# MCORD_AFE_EXT.net
KiCad netlist of a schematic drawn in Altium Designer
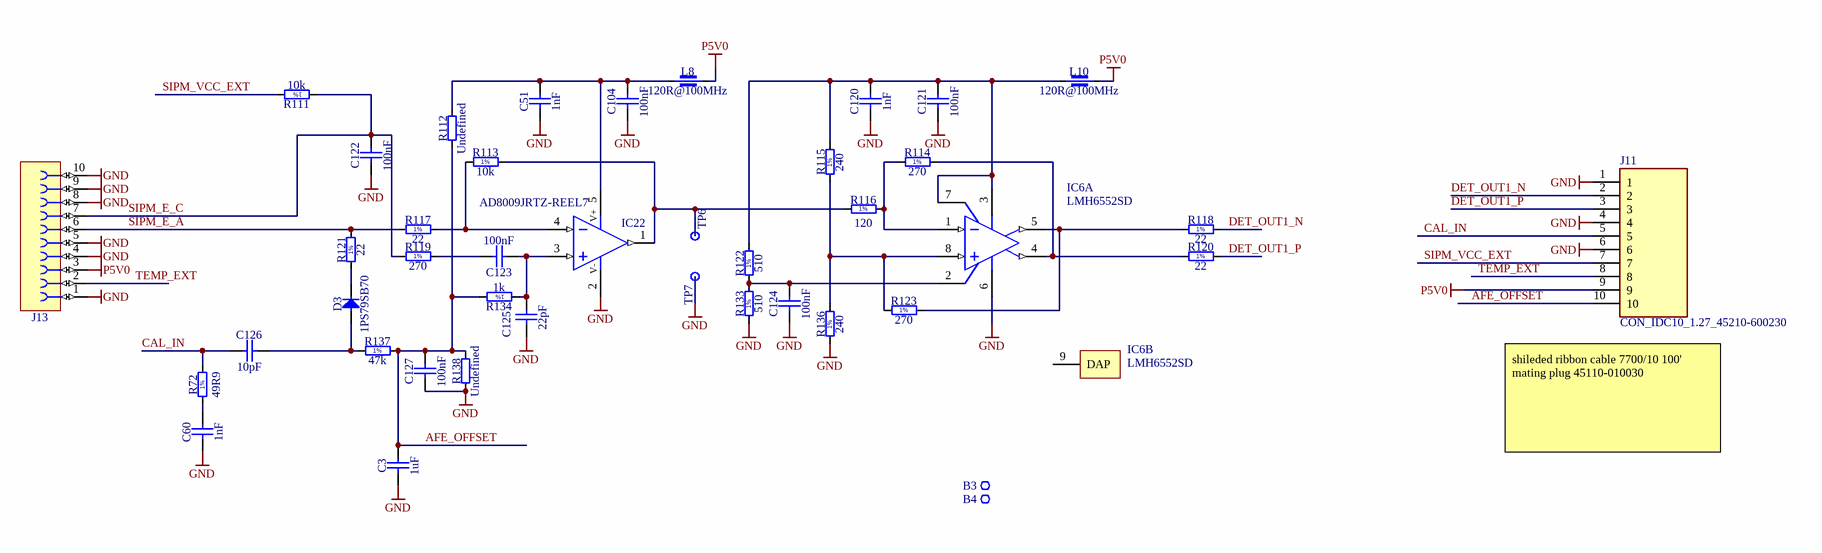
[diagram p0: MCORD_AFE_EXT.SchDoc]

(export (version "E")
  (design (tool "Eeschema 10.0.6"))
  (components
    (comp (ref "B3")
      (value "Plated Hole")
      (footprint "MTG320_550")
      (description "Single Terminal Socket")
      (fields (field (name "PART NUMBER") "PLATED_HOLE3.2_PAD5.5") (field (name "AUTHOR") "CERN DEM JMW"))
      (libsource (lib "Eletro-mechanical") (part "Single Terminal Socket"))
    )
    (comp (ref "B4")
      (value "Plated Hole")
      (footprint "MTG320_550")
      (description "Single Terminal Socket")
      (fields (field (name "PART NUMBER") "PLATED_HOLE3.2_PAD5.5") (field (name "AUTHOR") "CERN DEM JMW"))
      (libsource (lib "Eletro-mechanical") (part "Single Terminal Socket"))
    )
    (comp (ref "C3")
      (value "1uF")
      (footprint "CAPC1608X87N")
      (description "Non-polarised capacitor")
      (fields
        (field (name "PART NUMBER") "CC0603_1UF_16V_10%_X7R")
        (field (name "VOLTAGE") "16V")
        (field (name "AUTHOR") "CERN DEM JLC")
      )
      (libsource (lib "Capacitors") (part "Capacitor - non polarized"))
    )
    (comp (ref "C51")
      (value "1nF")
      (footprint "CAPC1005X55N")
      (description "Non-polarised capacitor")
      (fields
        (field (name "PART NUMBER") "CC0402_1NF_50V_5%_C0G")
        (field (name "VOLTAGE") "50V")
        (field (name "AUTHOR") "CERN DEM BC")
      )
      (libsource (lib "Capacitors") (part "Capacitor - non polarized"))
    )
    (comp (ref "C60")
      (value "1nF")
      (footprint "CAPC1005X55N")
      (description "Non-polarised capacitor")
      (fields
        (field (name "PART NUMBER") "CC0402_1NF_50V_5%_C0G")
        (field (name "VOLTAGE") "50V")
        (field (name "AUTHOR") "CERN DEM BC")
      )
      (libsource (lib "Capacitors") (part "Capacitor - non polarized"))
    )
    (comp (ref "C104")
      (value "100nF")
      (footprint "CAPC1005X55N")
      (description "Non-polarised capacitor")
      (fields
        (field (name "PART NUMBER") "CC0402_100NF_16V_10%_X7R")
        (field (name "VOLTAGE") "16V")
        (field (name "AUTHOR") "CERN DEM JLC")
      )
      (libsource (lib "Capacitors") (part "Capacitor - non polarized"))
    )
    (comp (ref "C120")
      (value "1nF")
      (footprint "CAPC1005X55N")
      (description "Non-polarised capacitor")
      (fields
        (field (name "PART NUMBER") "CC0402_1NF_50V_5%_C0G")
        (field (name "VOLTAGE") "50V")
        (field (name "AUTHOR") "CERN DEM BC")
      )
      (libsource (lib "Capacitors") (part "Capacitor - non polarized"))
    )
    (comp (ref "C121")
      (value "100nF")
      (footprint "CAPC1005X55N")
      (description "Non-polarised capacitor")
      (fields
        (field (name "PART NUMBER") "CC0402_100NF_16V_10%_X7R")
        (field (name "VOLTAGE") "16V")
        (field (name "AUTHOR") "CERN DEM JLC")
      )
      (libsource (lib "Capacitors") (part "Capacitor - non polarized"))
    )
    (comp (ref "C122")
      (value "100nF")
      (footprint "CAPC1608X90N")
      (description "Non-polarised capacitor")
      (fields
        (field (name "PART NUMBER") "CC0603_100NF_100V_10%_X7R")
        (field (name "VOLTAGE") "100V")
        (field (name "AUTHOR") "CERN DEM JLC")
      )
      (libsource (lib "Capacitors") (part "Capacitor - non polarized"))
    )
    (comp (ref "C123")
      (value "100nF")
      (footprint "CAPC1608X90N")
      (description "Non-polarised capacitor")
      (fields
        (field (name "PART NUMBER") "CC0603_100NF_100V_10%_X7R")
        (field (name "VOLTAGE") "100V")
        (field (name "AUTHOR") "CERN DEM JLC")
      )
      (libsource (lib "Capacitors") (part "Capacitor - non polarized"))
    )
    (comp (ref "C124")
      (value "100nF")
      (footprint "CAPC1005X55N")
      (description "Non-polarised capacitor")
      (fields
        (field (name "PART NUMBER") "CC0402_100NF_16V_10%_X7R")
        (field (name "VOLTAGE") "16V")
        (field (name "AUTHOR") "CERN DEM JLC")
      )
      (libsource (lib "Capacitors") (part "Capacitor - non polarized"))
    )
    (comp (ref "C125")
      (value "22pF")
      (footprint "CAPC1005X55N")
      (description "Non-polarised capacitor")
      (fields
        (field (name "PART NUMBER") "CC0402_22PF_50V_5%_C0G")
        (field (name "VOLTAGE") "50V")
        (field (name "AUTHOR") "CERN DEM JLC")
      )
      (libsource (lib "Capacitors") (part "Capacitor - non polarized"))
    )
    (comp (ref "C126")
      (value "10pF")
      (footprint "CAPC1608X87N")
      (description "Non-polarised capacitor")
      (fields
        (field (name "PART NUMBER") "CC0603_10PF_50V_5%_NP0")
        (field (name "VOLTAGE") "50V")
        (field (name "AUTHOR") "CERN DEM JLC")
      )
      (libsource (lib "Capacitors") (part "Capacitor - non polarized"))
    )
    (comp (ref "C127")
      (value "100nF")
      (footprint "CAPC1005X55N")
      (description "Non-polarised capacitor")
      (fields
        (field (name "PART NUMBER") "CC0402_100NF_16V_10%_X7R")
        (field (name "VOLTAGE") "16V")
        (field (name "AUTHOR") "CERN DEM JLC")
      )
      (libsource (lib "Capacitors") (part "Capacitor - non polarized"))
    )
    (comp (ref "D3")
      (value "1PS79SB70")
      (footprint "SODFL1608X65N")
      (description "Diode")
      (fields (field (name "VOLTAGE") "70V") (field (name "POWER") "70mA") (field (name "AUTHOR") "GK"))
      (libsource (lib "Diodes") (part "D_1PS79SB70"))
    )
    (comp (ref "IC6")
      (value "LMH6552SD")
      (footprint "SDA08C")
      (description "1.5 GHz Fully Differential Amplifier, 8-pin LLP")
      (fields (field (name "MANUFACTURER") "National Semiconductor"))
      (libsource (lib "Altium Content Vault") (part "AMP-DIFA-LMH6552-9"))
    )
    (comp (ref "IC22")
      (value "AD8009JRTZ-REEL7")
      (footprint "SOT95P280X145-5N")
      (description "Operational Amplifier")
      (fields (field (name "MANUFACTURER") "ANALOG DEVICES") (field (name "AUTHOR") "CERN DEM JLC"))
      (libsource (lib "ICs And Semiconductors") (part "Operational Amplifier Type7"))
    )
    (comp (ref "J11")
      (value "CON_IDC10_1.27_45210-600230")
      (footprint "SamacSys:SHDR10W38P127_2X5_1069X594X747P")
      (description "Connector")
      (fields
        (field (name "MANUFACTURER_PART_NUMBER") "45210-600230")
        (field (name "MOUSER PART NUMBER") "517-45210-600230")
      )
      (libsource (lib "LIBRARY_SCH") (part "CON_IDC10_1.27_45210-600230"))
    )
    (comp (ref "J13")
      (value "FFC/FPC")
      (footprint "MOLEX_52745-1097")
      (description "Connector 10 Female")
      (fields
        (field (name "PART NUMBER") "MOLEX_52745-1097")
        (field (name "MANUFACTURER") "MOLEX")
        (field (name "AUTHOR") "CERN DEM JLC")
      )
      (libsource (lib "Connectors") (part "Connector 10 Female"))
    )
    (comp (ref "L8")
      (value "120R@100MHz")
      (footprint "INDC1005X55N")
      (fields
        (field (name "PART NUMBER") "IND0402_MURATA_BLM15PX121SN1D")
        (field (name "POWER") "2A")
        (field (name "TOLERANCE") "±25%")
        (field (name "AUTHOR") "CERN DEM JMW")
      )
      (libsource (lib "Inductors & Transformers") (part "Ferrite Bead"))
    )
    (comp (ref "L10")
      (value "120R@100MHz")
      (footprint "INDC1005X55N")
      (fields
        (field (name "PART NUMBER") "IND0402_MURATA_BLM15PX121SN1D")
        (field (name "POWER") "2A")
        (field (name "TOLERANCE") "±25%")
        (field (name "AUTHOR") "CERN DEM JMW")
      )
      (libsource (lib "Inductors & Transformers") (part "Ferrite Bead"))
    )
    (comp (ref "R72")
      (value "49R9")
      (footprint "RESC1005X40N")
      (description "Resistor - 1%")
      (fields
        (field (name "PART NUMBER") "R0402_49R9_1%_0.0625W_100PPM")
        (field (name "POWER") "0.0625W")
        (field (name "AUTHOR") "CERN DEM JLC")
      )
      (libsource (lib "Resistors") (part "Resistor - 1%"))
    )
    (comp (ref "R111")
      (value "10k")
      (footprint "RESC1005X40N")
      (description "Resistor - 1%")
      (fields
        (field (name "PART NUMBER") "R0402_10K_1%_0.0625W_100PPM")
        (field (name "POWER") "0.0625W")
        (field (name "AUTHOR") "CERN DEM JLC")
      )
      (libsource (lib "Resistors") (part "Resistor - 1%"))
    )
    (comp (ref "R112")
      (value "Undefined")
      (footprint "RESC1005X40N")
      (description "Resistor")
      (fields (field (name "PART NUMBER") "R0402_NO-VALUE") (field (name "AUTHOR") "CERN DEM JLC"))
      (libsource (lib "Resistors") (part "Resistor"))
    )
    (comp (ref "R113")
      (value "10k")
      (footprint "RESC1005X40N")
      (description "Resistor - 1%")
      (fields
        (field (name "PART NUMBER") "R0402_10K_1%_0.0625W_100PPM")
        (field (name "POWER") "0.0625W")
        (field (name "AUTHOR") "CERN DEM JLC")
      )
      (libsource (lib "Resistors") (part "Resistor - 1%"))
    )
    (comp (ref "R114")
      (value "270")
      (footprint "RESC1005X40N")
      (description "Resistor - 1%")
      (fields
        (field (name "PART NUMBER") "R0402_270R_1%_0.0625W_100PPM")
        (field (name "POWER") "0.0625W")
        (field (name "AUTHOR") "CERN DEM JLC")
      )
      (libsource (lib "Resistors") (part "Resistor - 1%"))
    )
    (comp (ref "R115")
      (value "240")
      (footprint "RESC1005X40N")
      (description "Resistor - 1%")
      (fields
        (field (name "PART NUMBER") "R0402_240R_1%_0.0625W_100PPM")
        (field (name "POWER") "0.0625W")
        (field (name "AUTHOR") "CERN DEM JLC")
      )
      (libsource (lib "Resistors") (part "Resistor - 1%"))
    )
    (comp (ref "R116")
      (value "120")
      (footprint "RESC1005X40N")
      (description "Resistor - 1%")
      (fields
        (field (name "PART NUMBER") "R0402_120R_1%_0.0625W_100PPM")
        (field (name "POWER") "0.0625W")
        (field (name "AUTHOR") "CERN DEM JLC")
      )
      (libsource (lib "Resistors") (part "Resistor - 1%"))
    )
    (comp (ref "R117")
      (value "22")
      (footprint "RESC1608X55N")
      (description "Resistor - 1%")
      (fields
        (field (name "PART NUMBER") "R0603_22R_1%_0.1W_100PPM")
        (field (name "POWER") "0.1W")
        (field (name "AUTHOR") "CERN DEM JLC")
      )
      (libsource (lib "Resistors") (part "Resistor - 1%"))
    )
    (comp (ref "R118")
      (value "22")
      (footprint "RESC1608X55N")
      (description "Resistor - 1%")
      (fields
        (field (name "PART NUMBER") "R0603_22R_1%_0.1W_100PPM")
        (field (name "POWER") "0.1W")
        (field (name "AUTHOR") "CERN DEM JLC")
      )
      (libsource (lib "Resistors") (part "Resistor - 1%"))
    )
    (comp (ref "R119")
      (value "270")
      (footprint "RESC1005X40N")
      (description "Resistor - 1%")
      (fields
        (field (name "PART NUMBER") "R0402_270R_1%_0.0625W_100PPM")
        (field (name "POWER") "0.0625W")
        (field (name "AUTHOR") "CERN DEM JLC")
      )
      (libsource (lib "Resistors") (part "Resistor - 1%"))
    )
    (comp (ref "R120")
      (value "22")
      (footprint "RESC1608X55N")
      (description "Resistor - 1%")
      (fields
        (field (name "PART NUMBER") "R0603_22R_1%_0.1W_100PPM")
        (field (name "POWER") "0.1W")
        (field (name "AUTHOR") "CERN DEM JLC")
      )
      (libsource (lib "Resistors") (part "Resistor - 1%"))
    )
    (comp (ref "R121")
      (value "22")
      (footprint "RESC1608X55N")
      (description "Resistor - 1%")
      (fields
        (field (name "PART NUMBER") "R0603_22R_1%_0.1W_100PPM")
        (field (name "POWER") "0.1W")
        (field (name "AUTHOR") "CERN DEM JLC")
      )
      (libsource (lib "Resistors") (part "Resistor - 1%"))
    )
    (comp (ref "R122")
      (value "510")
      (footprint "RESC1005X40N")
      (description "Resistor - 1%")
      (fields
        (field (name "PART NUMBER") "R0402_510R_1%_0.0625W_100PPM")
        (field (name "POWER") "0.0625W")
        (field (name "AUTHOR") "CERN DEM JLC")
      )
      (libsource (lib "Resistors") (part "Resistor - 1%"))
    )
    (comp (ref "R123")
      (value "270")
      (footprint "RESC1005X40N")
      (description "Resistor - 1%")
      (fields
        (field (name "PART NUMBER") "R0402_270R_1%_0.0625W_100PPM")
        (field (name "POWER") "0.0625W")
        (field (name "AUTHOR") "CERN DEM JLC")
      )
      (libsource (lib "Resistors") (part "Resistor - 1%"))
    )
    (comp (ref "R133")
      (value "510")
      (footprint "RESC1005X40N")
      (description "Resistor - 1%")
      (fields
        (field (name "PART NUMBER") "R0402_510R_1%_0.0625W_100PPM")
        (field (name "POWER") "0.0625W")
        (field (name "AUTHOR") "CERN DEM JLC")
      )
      (libsource (lib "Resistors") (part "Resistor - 1%"))
    )
    (comp (ref "R134")
      (value "1k")
      (footprint "RESC1005X40N")
      (description "Resistor - 1%")
      (fields
        (field (name "PART NUMBER") "R0402_1K_1%_0.0625W_100PPM")
        (field (name "POWER") "0.0625W")
        (field (name "AUTHOR") "CERN DEM JLC")
      )
      (libsource (lib "Resistors") (part "Resistor - 1%"))
    )
    (comp (ref "R136")
      (value "240")
      (footprint "RESC1005X40N")
      (description "Resistor - 1%")
      (fields
        (field (name "PART NUMBER") "R0402_240R_1%_0.0625W_100PPM")
        (field (name "POWER") "0.0625W")
        (field (name "AUTHOR") "CERN DEM JLC")
      )
      (libsource (lib "Resistors") (part "Resistor - 1%"))
    )
    (comp (ref "R137")
      (value "47k")
      (footprint "RESC1005X40N")
      (description "Resistor - 1%")
      (fields
        (field (name "PART NUMBER") "R0402_47K_1%_0.0625W_100PPM")
        (field (name "POWER") "0.0625W")
        (field (name "AUTHOR") "CERN DEM JLC")
      )
      (libsource (lib "Resistors") (part "Resistor - 1%"))
    )
    (comp (ref "R138")
      (value "Undefined")
      (footprint "RESC1005X40N")
      (description "Resistor")
      (fields (field (name "PART NUMBER") "R0402_NO-VALUE") (field (name "AUTHOR") "CERN DEM JLC"))
      (libsource (lib "Resistors") (part "Resistor"))
    )
    (comp (ref "TP6")
      (value "Test Point")
      (footprint "TPS127")
      (fields (field (name "PART NUMBER") "SMD_PAD_1.27X1.27MM") (field (name "AUTHOR") "CERN DEM JLC"))
      (libsource (lib "Eletro-mechanical") (part "Test Point"))
    )
    (comp (ref "TP7")
      (value "Test Point")
      (footprint "TPS127")
      (fields (field (name "PART NUMBER") "SMD_PAD_1.27X1.27MM") (field (name "AUTHOR") "CERN DEM JLC"))
      (libsource (lib "Eletro-mechanical") (part "Test Point"))
    )
  )
  (nets
    (net (code "1") (name "/AFE_OFFSET") (class "Default")
      (node (ref "C127") (pin "2") (pinfunction "2_2") (pintype "passive"))
      (node (ref "C3") (pin "2") (pinfunction "2_2") (pintype "passive"))
      (node (ref "J11") (pin "10") (pinfunction "10_10") (pintype "passive"))
      (node (ref "R112") (pin "1") (pinfunction "1_1") (pintype "passive"))
      (node (ref "R134") (pin "2") (pinfunction "2_2") (pintype "passive"))
      (node (ref "R137") (pin "2") (pinfunction "2_2") (pintype "passive"))
      (node (ref "R138") (pin "2") (pinfunction "2_2") (pintype "passive"))
    )
    (net (code "2") (name "/CAL_IN") (class "Default")
      (node (ref "C126") (pin "1") (pinfunction "1_1") (pintype "passive"))
      (node (ref "J11") (pin "5") (pinfunction "5_5") (pintype "passive"))
      (node (ref "R72") (pin "2") (pinfunction "2_2") (pintype "passive"))
    )
    (net (code "3") (name "/DET_OUT1_N") (class "Default")
      (node (ref "J11") (pin "2") (pinfunction "2_2") (pintype "passive"))
      (node (ref "R118") (pin "2") (pinfunction "2_2") (pintype "passive"))
    )
    (net (code "4") (name "/DET_OUT1_P") (class "Default")
      (node (ref "J11") (pin "3") (pinfunction "3_3") (pintype "passive"))
      (node (ref "R120") (pin "2") (pinfunction "2_2") (pintype "passive"))
    )
    (net (code "5") (name "/SIPM_E_A") (class "Default")
      (node (ref "J13") (pin "6") (pinfunction "6_6") (pintype "bidirectional"))
      (node (ref "R117") (pin "1") (pinfunction "1_1") (pintype "passive"))
      (node (ref "R121") (pin "2") (pinfunction "2_2") (pintype "passive"))
    )
    (net (code "6") (name "/SIPM_E_C") (class "Default")
      (node (ref "C122") (pin "2") (pinfunction "2_2") (pintype "passive"))
      (node (ref "J13") (pin "7") (pinfunction "7_7") (pintype "bidirectional"))
      (node (ref "R111") (pin "1") (pinfunction "1_1") (pintype "passive"))
      (node (ref "R119") (pin "1") (pinfunction "1_1") (pintype "passive"))
    )
    (net (code "7") (name "/SIPM_VCC_EXT") (class "Default")
      (node (ref "J11") (pin "7") (pinfunction "7_7") (pintype "passive"))
      (node (ref "R111") (pin "2") (pinfunction "2_2") (pintype "passive"))
    )
    (net (code "8") (name "/TEMP_EXT") (class "Default")
      (node (ref "J11") (pin "8") (pinfunction "8_8") (pintype "passive"))
      (node (ref "J13") (pin "2") (pinfunction "2_2") (pintype "bidirectional"))
    )
    (net (code "9") (name "GND") (class "Default")
      (node (ref "C104") (pin "1") (pinfunction "1_1") (pintype "passive"))
      (node (ref "C120") (pin "1") (pinfunction "1_1") (pintype "passive"))
      (node (ref "C121") (pin "1") (pinfunction "1_1") (pintype "passive"))
      (node (ref "C122") (pin "1") (pinfunction "1_1") (pintype "passive"))
      (node (ref "C124") (pin "1") (pinfunction "1_1") (pintype "passive"))
      (node (ref "C125") (pin "1") (pinfunction "1_1") (pintype "passive"))
      (node (ref "C127") (pin "1") (pinfunction "1_1") (pintype "passive"))
      (node (ref "C3") (pin "1") (pinfunction "1_1") (pintype "passive"))
      (node (ref "C51") (pin "1") (pinfunction "1_1") (pintype "passive"))
      (node (ref "C60") (pin "1") (pinfunction "1_1") (pintype "passive"))
      (node (ref "IC22") (pin "2") (pinfunction "V-_2") (pintype "power_in"))
      (node (ref "IC6") (pin "6") (pinfunction "V-_6") (pintype "power_in"))
      (node (ref "J11") (pin "1") (pinfunction "1_1") (pintype "passive"))
      (node (ref "J11") (pin "4") (pinfunction "4_4") (pintype "passive"))
      (node (ref "J11") (pin "6") (pinfunction "6_6") (pintype "passive"))
      (node (ref "J13") (pin "1") (pinfunction "1_1") (pintype "bidirectional"))
      (node (ref "J13") (pin "10") (pinfunction "10_10") (pintype "bidirectional"))
      (node (ref "J13") (pin "4") (pinfunction "4_4") (pintype "bidirectional"))
      (node (ref "J13") (pin "5") (pinfunction "5_5") (pintype "bidirectional"))
      (node (ref "J13") (pin "8") (pinfunction "8_8") (pintype "bidirectional"))
      (node (ref "J13") (pin "9") (pinfunction "9_9") (pintype "bidirectional"))
      (node (ref "R133") (pin "1") (pinfunction "1_1") (pintype "passive"))
      (node (ref "R136") (pin "1") (pinfunction "1_1") (pintype "passive"))
      (node (ref "R138") (pin "1") (pinfunction "1_1") (pintype "passive"))
      (node (ref "TP7") (pin "1") (pinfunction "1_1") (pintype "bidirectional"))
    )
    (net (code "10") (name "Net-(C60-Pad2)") (class "Default")
      (node (ref "C60") (pin "2") (pinfunction "2_2") (pintype "passive"))
      (node (ref "R72") (pin "1") (pinfunction "1_1") (pintype "passive"))
    )
    (net (code "11") (name "Net-(C123-Pad2)") (class "Default")
      (node (ref "C123") (pin "2") (pinfunction "2_2") (pintype "passive"))
      (node (ref "R119") (pin "2") (pinfunction "2_2") (pintype "passive"))
    )
    (net (code "12") (name "Net-(D3-A)") (class "Default")
      (node (ref "C126") (pin "2") (pinfunction "2_2") (pintype "passive"))
      (node (ref "D3") (pin "2") (pinfunction "A_2") (pintype "passive"))
      (node (ref "R137") (pin "1") (pinfunction "1_1") (pintype "passive"))
    )
    (net (code "13") (name "Net-(D3-C)") (class "Default")
      (node (ref "D3") (pin "1") (pinfunction "C_1") (pintype "passive"))
      (node (ref "R121") (pin "1") (pinfunction "1_1") (pintype "passive"))
    )
    (net (code "14") (name "Net-(IC6A-EN)") (class "Default")
      (node (ref "C120") (pin "2") (pinfunction "2_2") (pintype "passive"))
      (node (ref "C121") (pin "2") (pinfunction "2_2") (pintype "passive"))
      (node (ref "IC6") (pin "3") (pinfunction "V+_3") (pintype "power_in"))
      (node (ref "IC6") (pin "7") (pinfunction "EN_7") (pintype "passive"))
      (node (ref "L10") (pin "1") (pinfunction "1_1") (pintype "passive"))
      (node (ref "R115") (pin "2") (pinfunction "2_2") (pintype "passive"))
      (node (ref "R122") (pin "2") (pinfunction "2_2") (pintype "passive"))
    )
    (net (code "15") (name "Net-(IC6A-IN+)") (class "Default")
      (node (ref "IC6") (pin "8") (pinfunction "IN+_8") (pintype "input"))
      (node (ref "R115") (pin "1") (pinfunction "1_1") (pintype "passive"))
      (node (ref "R123") (pin "1") (pinfunction "1_1") (pintype "passive"))
      (node (ref "R136") (pin "2") (pinfunction "2_2") (pintype "passive"))
    )
    (net (code "16") (name "Net-(IC6A-IN-)") (class "Default")
      (node (ref "IC6") (pin "1") (pinfunction "IN-_1") (pintype "input"))
      (node (ref "R114") (pin "1") (pinfunction "1_1") (pintype "passive"))
      (node (ref "R116") (pin "2") (pinfunction "2_2") (pintype "passive"))
    )
    (net (code "17") (name "Net-(IC6A-OUT+)") (class "Default")
      (node (ref "IC6") (pin "4") (pinfunction "OUT+_4") (pintype "output"))
      (node (ref "R114") (pin "2") (pinfunction "2_2") (pintype "passive"))
      (node (ref "R120") (pin "1") (pinfunction "1_1") (pintype "passive"))
    )
    (net (code "18") (name "Net-(IC6A-OUT-)") (class "Default")
      (node (ref "IC6") (pin "5") (pinfunction "OUT-_5") (pintype "output"))
      (node (ref "R118") (pin "1") (pinfunction "1_1") (pintype "passive"))
      (node (ref "R123") (pin "2") (pinfunction "2_2") (pintype "passive"))
    )
    (net (code "19") (name "Net-(IC6A-VCM)") (class "Default")
      (node (ref "C124") (pin "2") (pinfunction "2_2") (pintype "passive"))
      (node (ref "IC6") (pin "2") (pinfunction "VCM_2") (pintype "passive"))
      (node (ref "R122") (pin "1") (pinfunction "1_1") (pintype "passive"))
      (node (ref "R133") (pin "2") (pinfunction "2_2") (pintype "passive"))
    )
    (net (code "20") (name "Net-(IC22-IN+)") (class "Default")
      (node (ref "C123") (pin "1") (pinfunction "1_1") (pintype "passive"))
      (node (ref "C125") (pin "2") (pinfunction "2_2") (pintype "passive"))
      (node (ref "IC22") (pin "3") (pinfunction "IN+_3") (pintype "input"))
      (node (ref "R134") (pin "1") (pinfunction "1_1") (pintype "passive"))
    )
    (net (code "21") (name "Net-(IC22-IN-)") (class "Default")
      (node (ref "IC22") (pin "4") (pinfunction "IN-_4") (pintype "input"))
      (node (ref "R113") (pin "1") (pinfunction "1_1") (pintype "passive"))
      (node (ref "R117") (pin "2") (pinfunction "2_2") (pintype "passive"))
    )
    (net (code "22") (name "Net-(IC22-OUT)") (class "Default")
      (node (ref "IC22") (pin "1") (pinfunction "OUT_1") (pintype "output"))
      (node (ref "R113") (pin "2") (pinfunction "2_2") (pintype "passive"))
      (node (ref "R116") (pin "1") (pinfunction "1_1") (pintype "passive"))
      (node (ref "TP6") (pin "1") (pinfunction "1_1") (pintype "bidirectional"))
    )
    (net (code "23") (name "Net-(IC22-V+)") (class "Default")
      (node (ref "C104") (pin "2") (pinfunction "2_2") (pintype "passive"))
      (node (ref "C51") (pin "2") (pinfunction "2_2") (pintype "passive"))
      (node (ref "IC22") (pin "5") (pinfunction "V+_5") (pintype "power_in"))
      (node (ref "L8") (pin "1") (pinfunction "1_1") (pintype "passive"))
      (node (ref "R112") (pin "2") (pinfunction "2_2") (pintype "passive"))
    )
    (net (code "24") (name "P5V0") (class "Default")
      (node (ref "J11") (pin "9") (pinfunction "9_9") (pintype "passive"))
      (node (ref "J13") (pin "3") (pinfunction "3_3") (pintype "bidirectional"))
      (node (ref "L10") (pin "2") (pinfunction "2_2") (pintype "passive"))
      (node (ref "L8") (pin "2") (pinfunction "2_2") (pintype "passive"))
    )
    (net (code "25") (name "unconnected-(B3-Pad1)") (class "Default")
      (node (ref "B3") (pin "1") (pinfunction "1_1") (pintype "bidirectional"))
    )
    (net (code "26") (name "unconnected-(B4-Pad1)") (class "Default")
      (node (ref "B4") (pin "1") (pinfunction "1_1") (pintype "bidirectional"))
    )
    (net (code "27") (name "unconnected-(IC6B-DAP-Pad9)") (class "Default")
      (node (ref "IC6") (pin "9") (pinfunction "DAP_9") (pintype "passive"))
    )
  )
)
